# electric-imp-shield.net
KiCad netlist of a schematic drawn in EAGLE
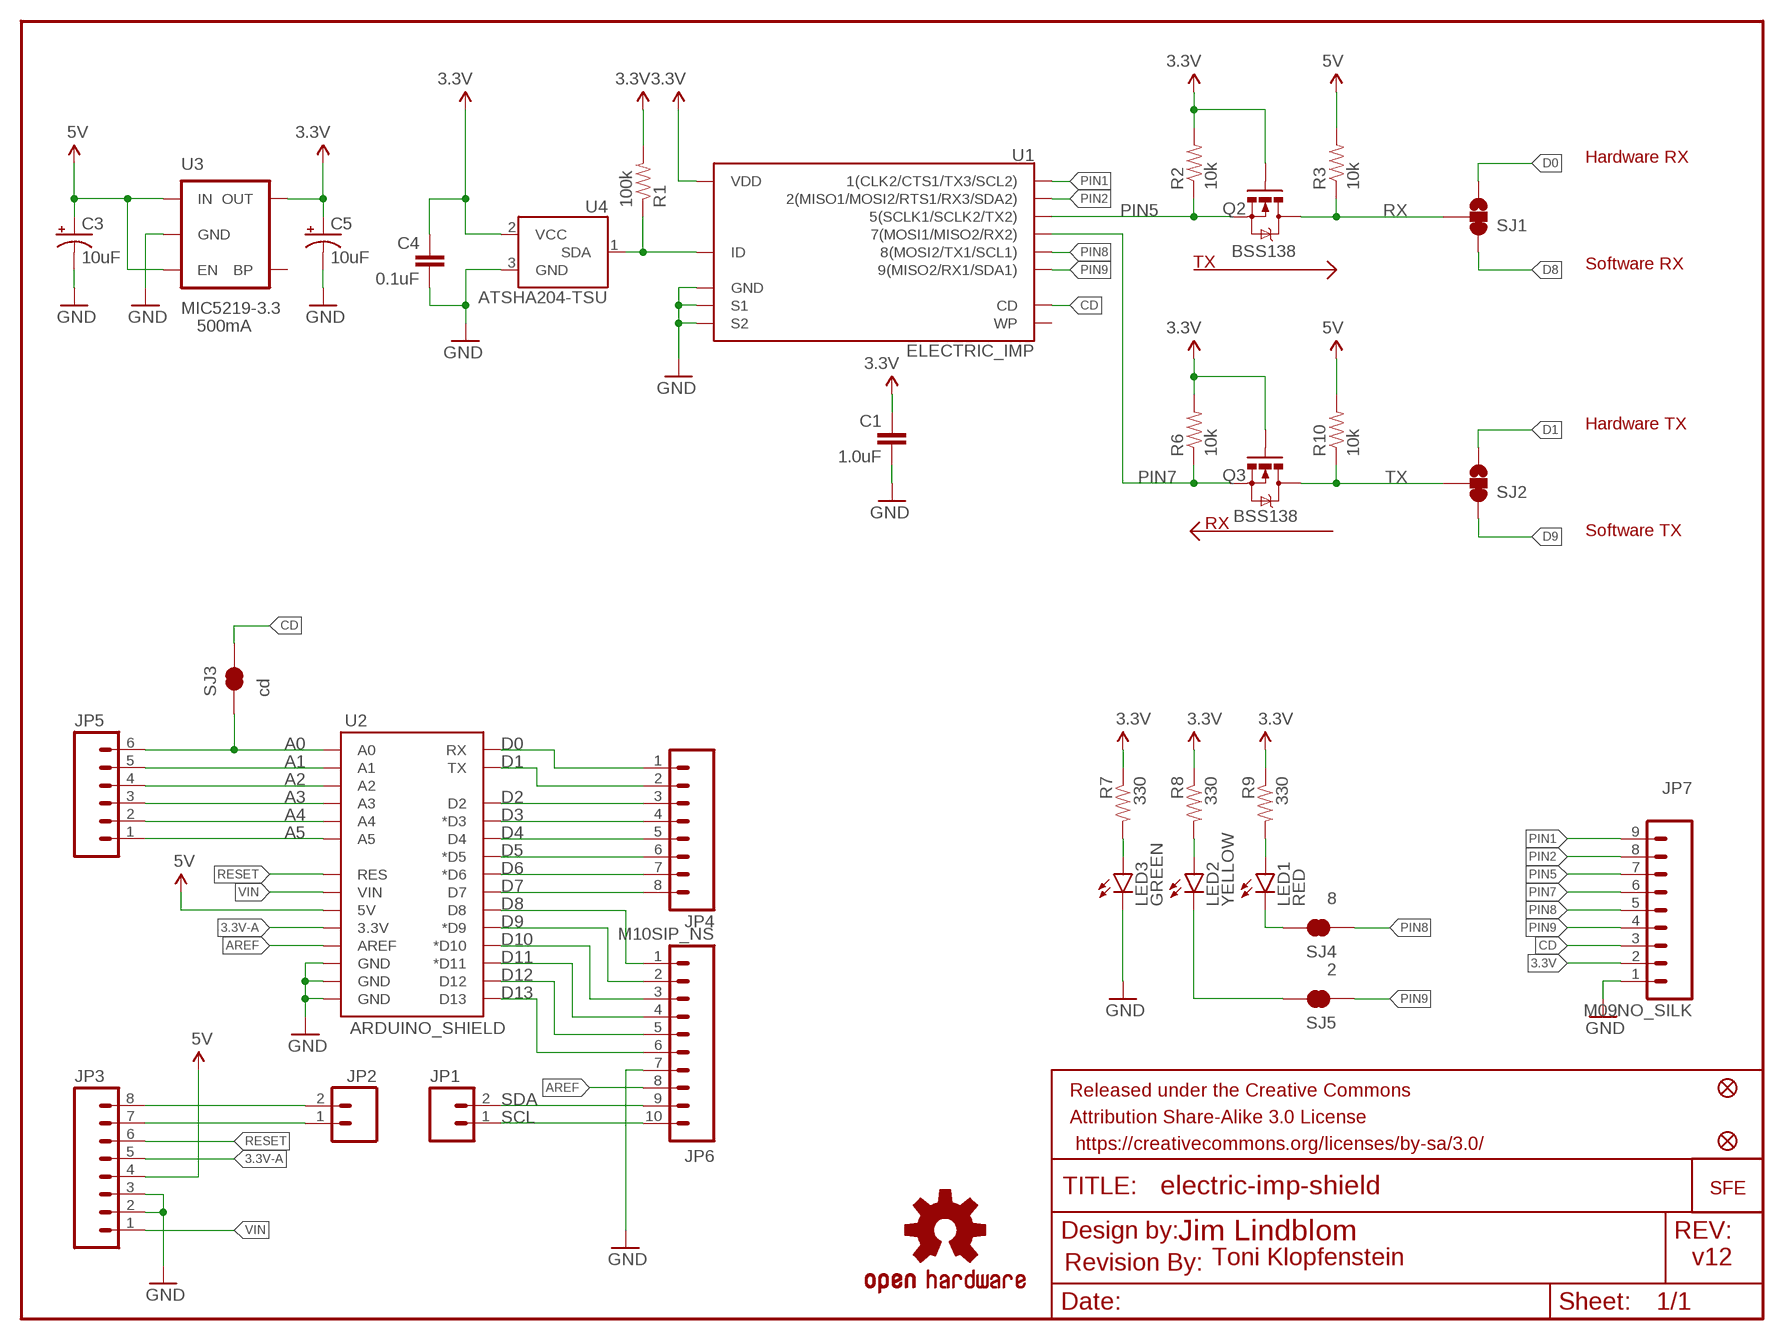
[diagram p0: schematic, sheet 1]

(export (version "E")
  (design (tool "Eeschema 10.0.6"))
  (components
    (comp (ref "C1")
      (value "1.0uF")
      (footprint "eagle-import:0603-CAP")
      (libsource (lib "eagle-import") (part "1.0UF-16V-10%(0603)"))
    )
    (comp (ref "C3")
      (value "10uF")
      (footprint "eagle-import:EIA3216")
      (libsource (lib "eagle-import") (part "10UF-16V-10%(TANT)"))
    )
    (comp (ref "C4")
      (value "0.1uF")
      (footprint "eagle-import:0603-CAP")
      (libsource (lib "eagle-import") (part "0.1UF-25V(+80/-20%)(0603)"))
    )
    (comp (ref "C5")
      (value "10uF")
      (footprint "eagle-import:EIA3216")
      (libsource (lib "eagle-import") (part "10UF-16V-10%(TANT)"))
    )
    (comp (ref "FID1")
      (value "FIDUCIAL1X2")
      (footprint "eagle-import:FIDUCIAL-1X2")
      (libsource (lib "eagle-import") (part "FIDUCIAL1X2"))
    )
    (comp (ref "FID2")
      (value "FIDUCIAL1X2")
      (footprint "eagle-import:FIDUCIAL-1X2")
      (libsource (lib "eagle-import") (part "FIDUCIAL1X2"))
    )
    (comp (ref "FRAME1")
      (value "FRAME-LETTER")
      (footprint "eagle-import:CREATIVE_COMMONS")
      (libsource (lib "eagle-import") (part "FRAME-LETTER"))
    )
    (comp (ref "JP1")
      (value "M021X02_NO_SILK")
      (footprint "eagle-import:1X02_NO_SILK")
      (libsource (lib "eagle-import") (part "M021X02_NO_SILK"))
    )
    (comp (ref "JP2")
      (value "M021X02_NO_SILK")
      (footprint "eagle-import:1X02_NO_SILK")
      (libsource (lib "eagle-import") (part "M021X02_NO_SILK"))
    )
    (comp (ref "JP3")
      (value "M08SIP_NS")
      (footprint "eagle-import:1X08_NO_SILK")
      (libsource (lib "eagle-import") (part "M08SIP_NS"))
    )
    (comp (ref "JP4")
      (value "M08SIP_NS")
      (footprint "eagle-import:1X08_NO_SILK")
      (libsource (lib "eagle-import") (part "M08SIP_NS"))
    )
    (comp (ref "JP5")
      (value "M06SIP_NS")
      (footprint "eagle-import:1X06_NO_SILK")
      (libsource (lib "eagle-import") (part "M06SIP_NS"))
    )
    (comp (ref "JP6")
      (value "M10SIP_NS")
      (footprint "eagle-import:1X10_NO_SILK")
      (libsource (lib "eagle-import") (part "M10SIP_NS"))
    )
    (comp (ref "JP7")
      (value "M09NO_SILK")
      (footprint "eagle-import:1X09_NO_SILK")
      (libsource (lib "eagle-import") (part "M09NO_SILK"))
    )
    (comp (ref "JP10")
      (value "LOGO-SFENW2")
      (footprint "eagle-import:SFE-NEW-WEB")
      (libsource (lib "eagle-import") (part "LOGO-SFENW2"))
    )
    (comp (ref "LED1")
      (value "RED")
      (footprint "eagle-import:LED-0603")
      (libsource (lib "eagle-import") (part "LED-RED0603"))
    )
    (comp (ref "LED2")
      (value "YELLOW")
      (footprint "eagle-import:LED-0603")
      (libsource (lib "eagle-import") (part "LED-YELLOW0603"))
    )
    (comp (ref "LED3")
      (value "GREEN")
      (footprint "eagle-import:LED-0603")
      (libsource (lib "eagle-import") (part "LED-GREEN0603"))
    )
    (comp (ref "Q2")
      (value "BSS138")
      (footprint "eagle-import:SOT23-3")
      (libsource (lib "eagle-import") (part "MOSFET-NCHANNELSMD"))
    )
    (comp (ref "Q3")
      (value "BSS138")
      (footprint "eagle-import:SOT23-3")
      (libsource (lib "eagle-import") (part "MOSFET-NCHANNELSMD"))
    )
    (comp (ref "R1")
      (value "100k")
      (footprint "eagle-import:0603-RES")
      (libsource (lib "eagle-import") (part "100KOHM1/10W1%(0603)"))
    )
    (comp (ref "R2")
      (value "10k")
      (footprint "eagle-import:0603-RES")
      (libsource (lib "eagle-import") (part "10KOHM1/10W1%(0603)0603"))
    )
    (comp (ref "R3")
      (value "10k")
      (footprint "eagle-import:0603-RES")
      (libsource (lib "eagle-import") (part "10KOHM1/10W1%(0603)0603"))
    )
    (comp (ref "R6")
      (value "10k")
      (footprint "eagle-import:0603-RES")
      (libsource (lib "eagle-import") (part "10KOHM1/10W1%(0603)0603"))
    )
    (comp (ref "R7")
      (value "330")
      (footprint "eagle-import:0603-RES")
      (libsource (lib "eagle-import") (part "330OHM1/10W1%(0603)"))
    )
    (comp (ref "R8")
      (value "330")
      (footprint "eagle-import:0603-RES")
      (libsource (lib "eagle-import") (part "330OHM1/10W1%(0603)"))
    )
    (comp (ref "R9")
      (value "330")
      (footprint "eagle-import:0603-RES")
      (libsource (lib "eagle-import") (part "330OHM1/10W1%(0603)"))
    )
    (comp (ref "R10")
      (value "10k")
      (footprint "eagle-import:0603-RES")
      (libsource (lib "eagle-import") (part "10KOHM1/10W1%(0603)0603"))
    )
    (comp (ref "SJ1")
      (value "SOLDERJUMPER_2WAYS")
      (footprint "eagle-import:SJ_3")
      (libsource (lib "eagle-import") (part "SOLDERJUMPER_2WAYS"))
    )
    (comp (ref "SJ2")
      (value "SOLDERJUMPER_2WAYS")
      (footprint "eagle-import:SJ_3")
      (libsource (lib "eagle-import") (part "SOLDERJUMPER_2WAYS"))
    )
    (comp (ref "SJ3")
      (value "cd")
      (footprint "eagle-import:SJ_2S-TRACE")
      (libsource (lib "eagle-import") (part "SOLDERJUMPERTRACE"))
    )
    (comp (ref "SJ4")
      (value "8")
      (footprint "eagle-import:SJ_2S-TRACE")
      (libsource (lib "eagle-import") (part "SOLDERJUMPERTRACE"))
    )
    (comp (ref "SJ5")
      (value "2")
      (footprint "eagle-import:SJ_2S-TRACE")
      (libsource (lib "eagle-import") (part "SOLDERJUMPERTRACE"))
    )
    (comp (ref "U$6")
      (value "REVISION")
      (footprint "eagle-import:REVISION")
      (libsource (lib "eagle-import") (part "REVISION"))
    )
    (comp (ref "U$7")
      (value "OSHW-LOGOS")
      (footprint "eagle-import:OSHW-LOGO-S")
      (libsource (lib "eagle-import") (part "OSHW-LOGOS"))
    )
    (comp (ref "U1")
      (value "ELECTRIC_IMP")
      (footprint "eagle-import:SD_1_1")
      (libsource (lib "eagle-import") (part "ELECTRIC_IMP"))
    )
    (comp (ref "U2")
      (value "ARDUINO_SHIELD")
      (footprint "eagle-import:DUEMILANOVE_SHIELD_NOHOLES_NOLABELS")
      (libsource (lib "eagle-import") (part "ARDUINO_SHIELDNOHOLESORLABELS"))
    )
    (comp (ref "U3")
      (value "MIC5219-3.3")
      (footprint "eagle-import:SOT23-5")
      (libsource (lib "eagle-import") (part "V_REG_LDOSMD"))
    )
    (comp (ref "U4")
      (value "ATSHA204-TSU")
      (footprint "eagle-import:SOT23-3")
      (libsource (lib "eagle-import") (part "ATSHA204-TSU"))
    )
  )
  (nets
    (net (code "1") (name "/A0") (class "Default")
      (node (ref "JP5") (pin "6") (pinfunction "6_6") (pintype "passive"))
      (node (ref "SJ3") (pin "1") (pinfunction "1_1") (pintype "passive"))
      (node (ref "U2") (pin "A0") (pinfunction "A0_A0") (pintype "bidirectional"))
    )
    (net (code "2") (name "/A1") (class "Default")
      (node (ref "JP5") (pin "5") (pinfunction "5_5") (pintype "passive"))
      (node (ref "U2") (pin "A1") (pinfunction "A1_A1") (pintype "bidirectional"))
    )
    (net (code "3") (name "/A2") (class "Default")
      (node (ref "JP5") (pin "4") (pinfunction "4_4") (pintype "passive"))
      (node (ref "U2") (pin "A2") (pinfunction "A2_A2") (pintype "bidirectional"))
    )
    (net (code "4") (name "/A3") (class "Default")
      (node (ref "JP5") (pin "3") (pinfunction "3_3") (pintype "passive"))
      (node (ref "U2") (pin "A3") (pinfunction "A3_A3") (pintype "bidirectional"))
    )
    (net (code "5") (name "/A4") (class "Default")
      (node (ref "JP5") (pin "2") (pinfunction "2_2") (pintype "passive"))
      (node (ref "U2") (pin "A4") (pinfunction "A4_A4") (pintype "bidirectional"))
    )
    (net (code "6") (name "/A5") (class "Default")
      (node (ref "JP5") (pin "1") (pinfunction "1_1") (pintype "passive"))
      (node (ref "U2") (pin "A5") (pinfunction "A5_A5") (pintype "bidirectional"))
    )
    (net (code "7") (name "/D2") (class "Default")
      (node (ref "JP4") (pin "3") (pinfunction "3_3") (pintype "passive"))
      (node (ref "U2") (pin "D2") (pinfunction "D2_D2") (pintype "bidirectional"))
    )
    (net (code "8") (name "/D3") (class "Default")
      (node (ref "JP4") (pin "4") (pinfunction "4_4") (pintype "passive"))
      (node (ref "U2") (pin "D3") (pinfunction "*D3_D3") (pintype "bidirectional"))
    )
    (net (code "9") (name "/D4") (class "Default")
      (node (ref "JP4") (pin "5") (pinfunction "5_5") (pintype "passive"))
      (node (ref "U2") (pin "D4") (pinfunction "D4_D4") (pintype "bidirectional"))
    )
    (net (code "10") (name "/D5") (class "Default")
      (node (ref "JP4") (pin "6") (pinfunction "6_6") (pintype "passive"))
      (node (ref "U2") (pin "D5") (pinfunction "*D5_D5") (pintype "bidirectional"))
    )
    (net (code "11") (name "/D6") (class "Default")
      (node (ref "JP4") (pin "7") (pinfunction "7_7") (pintype "passive"))
      (node (ref "U2") (pin "D6") (pinfunction "*D6_D6") (pintype "bidirectional"))
    )
    (net (code "12") (name "/D7") (class "Default")
      (node (ref "JP4") (pin "8") (pinfunction "8_8") (pintype "passive"))
      (node (ref "U2") (pin "D7") (pinfunction "D7_D7") (pintype "bidirectional"))
    )
    (net (code "13") (name "/D10") (class "Default")
      (node (ref "JP6") (pin "3") (pinfunction "3_3") (pintype "passive"))
      (node (ref "U2") (pin "D10") (pinfunction "*D10_D10") (pintype "bidirectional"))
    )
    (net (code "14") (name "/D11") (class "Default")
      (node (ref "JP6") (pin "4") (pinfunction "4_4") (pintype "passive"))
      (node (ref "U2") (pin "D11") (pinfunction "*D11_D11") (pintype "bidirectional"))
    )
    (net (code "15") (name "/D12") (class "Default")
      (node (ref "JP6") (pin "5") (pinfunction "5_5") (pintype "passive"))
      (node (ref "U2") (pin "D12") (pinfunction "D12_D12") (pintype "bidirectional"))
    )
    (net (code "16") (name "/D13") (class "Default")
      (node (ref "JP6") (pin "6") (pinfunction "6_6") (pintype "passive"))
      (node (ref "U2") (pin "D13") (pinfunction "D13_D13") (pintype "bidirectional"))
    )
    (net (code "17") (name "/RX") (class "Default")
      (node (ref "Q2") (pin "3") (pinfunction "D_3") (pintype "passive"))
      (node (ref "R3") (pin "1") (pinfunction "1_1") (pintype "passive"))
      (node (ref "SJ1") (pin "2") (pinfunction "2_2") (pintype "passive"))
    )
    (net (code "18") (name "/SCL") (class "Default")
      (node (ref "JP1") (pin "1") (pinfunction "1_1") (pintype "passive"))
      (node (ref "JP6") (pin "10") (pinfunction "10_10") (pintype "passive"))
    )
    (net (code "19") (name "/SDA") (class "Default")
      (node (ref "JP1") (pin "2") (pinfunction "2_2") (pintype "passive"))
      (node (ref "JP6") (pin "9") (pinfunction "9_9") (pintype "passive"))
    )
    (net (code "20") (name "/TX") (class "Default")
      (node (ref "Q3") (pin "3") (pinfunction "D_3") (pintype "passive"))
      (node (ref "R10") (pin "1") (pinfunction "1_1") (pintype "passive"))
      (node (ref "SJ2") (pin "2") (pinfunction "2_2") (pintype "passive"))
    )
    (net (code "21") (name "3.3V") (class "Default")
      (node (ref "C1") (pin "1") (pinfunction "1_1") (pintype "passive"))
      (node (ref "C4") (pin "1") (pinfunction "1_1") (pintype "passive"))
      (node (ref "C5") (pin "A") (pinfunction "+_A") (pintype "passive"))
      (node (ref "JP7") (pin "2") (pinfunction "2_2") (pintype "passive"))
      (node (ref "Q2") (pin "1") (pinfunction "G_1") (pintype "passive"))
      (node (ref "Q3") (pin "1") (pinfunction "G_1") (pintype "passive"))
      (node (ref "R1") (pin "2") (pinfunction "2_2") (pintype "passive"))
      (node (ref "R2") (pin "2") (pinfunction "2_2") (pintype "passive"))
      (node (ref "R6") (pin "2") (pinfunction "2_2") (pintype "passive"))
      (node (ref "R7") (pin "1") (pinfunction "1_1") (pintype "passive"))
      (node (ref "R8") (pin "1") (pinfunction "1_1") (pintype "passive"))
      (node (ref "R9") (pin "1") (pinfunction "1_1") (pintype "passive"))
      (node (ref "U1") (pin "4") (pinfunction "VDD_4") (pintype "bidirectional"))
      (node (ref "U3") (pin "5") (pinfunction "OUT_5") (pintype "passive"))
      (node (ref "U4") (pin "2") (pinfunction "VCC_2") (pintype "bidirectional"))
    )
    (net (code "22") (name "3.3V-A") (class "Default")
      (node (ref "JP3") (pin "5") (pinfunction "5_5") (pintype "passive"))
      (node (ref "U2") (pin "3.3V") (pinfunction "3.3V_3.3V") (pintype "bidirectional"))
    )
    (net (code "23") (name "5V") (class "Default")
      (node (ref "C3") (pin "A") (pinfunction "+_A") (pintype "passive"))
      (node (ref "JP3") (pin "4") (pinfunction "4_4") (pintype "passive"))
      (node (ref "R10") (pin "2") (pinfunction "2_2") (pintype "passive"))
      (node (ref "R3") (pin "2") (pinfunction "2_2") (pintype "passive"))
      (node (ref "U2") (pin "5V") (pinfunction "5V_5V") (pintype "bidirectional"))
      (node (ref "U3") (pin "1") (pinfunction "IN_1") (pintype "input"))
      (node (ref "U3") (pin "3") (pinfunction "EN_3") (pintype "input"))
    )
    (net (code "24") (name "AREF") (class "Default")
      (node (ref "JP6") (pin "8") (pinfunction "8_8") (pintype "passive"))
      (node (ref "U2") (pin "AREF") (pinfunction "AREF_AREF") (pintype "bidirectional"))
    )
    (net (code "25") (name "CD") (class "Default")
      (node (ref "JP7") (pin "3") (pinfunction "3_3") (pintype "passive"))
      (node (ref "SJ3") (pin "2") (pinfunction "2_2") (pintype "passive"))
      (node (ref "U1") (pin "CD") (pinfunction "CD_CD") (pintype "bidirectional"))
    )
    (net (code "26") (name "D0") (class "Default")
      (node (ref "JP4") (pin "1") (pinfunction "1_1") (pintype "passive"))
      (node (ref "SJ1") (pin "3") (pinfunction "3_3") (pintype "passive"))
      (node (ref "U2") (pin "RX") (pinfunction "RX_RX") (pintype "bidirectional"))
    )
    (net (code "27") (name "D1") (class "Default")
      (node (ref "JP4") (pin "2") (pinfunction "2_2") (pintype "passive"))
      (node (ref "SJ2") (pin "3") (pinfunction "3_3") (pintype "passive"))
      (node (ref "U2") (pin "TX") (pinfunction "TX_TX") (pintype "bidirectional"))
    )
    (net (code "28") (name "D8") (class "Default")
      (node (ref "JP6") (pin "1") (pinfunction "1_1") (pintype "passive"))
      (node (ref "SJ1") (pin "1") (pinfunction "1_1") (pintype "passive"))
      (node (ref "U2") (pin "D8") (pinfunction "D8_D8") (pintype "bidirectional"))
    )
    (net (code "29") (name "D9") (class "Default")
      (node (ref "JP6") (pin "2") (pinfunction "2_2") (pintype "passive"))
      (node (ref "SJ2") (pin "1") (pinfunction "1_1") (pintype "passive"))
      (node (ref "U2") (pin "D9") (pinfunction "*D9_D9") (pintype "bidirectional"))
    )
    (net (code "30") (name "GND") (class "Default")
      (node (ref "C1") (pin "2") (pinfunction "2_2") (pintype "passive"))
      (node (ref "C3") (pin "C") (pinfunction "-_C") (pintype "passive"))
      (node (ref "C4") (pin "2") (pinfunction "2_2") (pintype "passive"))
      (node (ref "C5") (pin "C") (pinfunction "-_C") (pintype "passive"))
      (node (ref "JP3") (pin "2") (pinfunction "2_2") (pintype "passive"))
      (node (ref "JP3") (pin "3") (pinfunction "3_3") (pintype "passive"))
      (node (ref "JP6") (pin "7") (pinfunction "7_7") (pintype "passive"))
      (node (ref "JP7") (pin "1") (pinfunction "1_1") (pintype "passive"))
      (node (ref "LED3") (pin "C") (pinfunction "C_C") (pintype "passive"))
      (node (ref "U1") (pin "3") (pinfunction "GND_3") (pintype "bidirectional"))
      (node (ref "U1") (pin "SH@1") (pinfunction "S1_SH@1") (pintype "bidirectional"))
      (node (ref "U1") (pin "SH@2") (pinfunction "S2_SH@2") (pintype "bidirectional"))
      (node (ref "U2") (pin "GND@0") (pinfunction "GND_GND@0") (pintype "bidirectional"))
      (node (ref "U2") (pin "GND@1") (pinfunction "GND_GND@1") (pintype "bidirectional"))
      (node (ref "U2") (pin "GND@2") (pinfunction "GND_GND@2") (pintype "bidirectional"))
      (node (ref "U3") (pin "2") (pinfunction "GND_2") (pintype "input"))
      (node (ref "U4") (pin "3") (pinfunction "GND_3") (pintype "bidirectional"))
    )
    (net (code "31") (name "Net-(JP2-Pad1)") (class "Default")
      (node (ref "JP2") (pin "1") (pinfunction "1_1") (pintype "passive"))
      (node (ref "JP3") (pin "7") (pinfunction "7_7") (pintype "passive"))
    )
    (net (code "32") (name "Net-(JP2-Pad2)") (class "Default")
      (node (ref "JP2") (pin "2") (pinfunction "2_2") (pintype "passive"))
      (node (ref "JP3") (pin "8") (pinfunction "8_8") (pintype "passive"))
    )
    (net (code "33") (name "Net-(LED1-PadA)") (class "Default")
      (node (ref "LED1") (pin "A") (pinfunction "A_A") (pintype "passive"))
      (node (ref "R9") (pin "2") (pinfunction "2_2") (pintype "passive"))
    )
    (net (code "34") (name "Net-(LED1-PadC)") (class "Default")
      (node (ref "LED1") (pin "C") (pinfunction "C_C") (pintype "passive"))
      (node (ref "SJ4") (pin "2") (pinfunction "2_2") (pintype "passive"))
    )
    (net (code "35") (name "Net-(LED2-PadA)") (class "Default")
      (node (ref "LED2") (pin "A") (pinfunction "A_A") (pintype "passive"))
      (node (ref "R8") (pin "2") (pinfunction "2_2") (pintype "passive"))
    )
    (net (code "36") (name "Net-(LED2-PadC)") (class "Default")
      (node (ref "LED2") (pin "C") (pinfunction "C_C") (pintype "passive"))
      (node (ref "SJ5") (pin "2") (pinfunction "2_2") (pintype "passive"))
    )
    (net (code "37") (name "Net-(LED3-PadA)") (class "Default")
      (node (ref "LED3") (pin "A") (pinfunction "A_A") (pintype "passive"))
      (node (ref "R7") (pin "2") (pinfunction "2_2") (pintype "passive"))
    )
    (net (code "38") (name "Net-(U1-ID)") (class "Default")
      (node (ref "R1") (pin "1") (pinfunction "1_1") (pintype "passive"))
      (node (ref "U1") (pin "6") (pinfunction "ID_6") (pintype "bidirectional"))
      (node (ref "U4") (pin "1") (pinfunction "SDA_1") (pintype "bidirectional"))
    )
    (net (code "39") (name "PIN1") (class "Default")
      (node (ref "JP7") (pin "9") (pinfunction "9_9") (pintype "passive"))
      (node (ref "U1") (pin "1") (pinfunction "1(CLK2/CTS1/TX3/SCL2)_1") (pintype "bidirectional"))
    )
    (net (code "40") (name "PIN2") (class "Default")
      (node (ref "JP7") (pin "8") (pinfunction "8_8") (pintype "passive"))
      (node (ref "U1") (pin "2") (pinfunction "2(MISO1/MOSI2/RTS1/RX3/SDA2)_2") (pintype "bidirectional"))
    )
    (net (code "41") (name "PIN5") (class "Default")
      (node (ref "JP7") (pin "7") (pinfunction "7_7") (pintype "passive"))
      (node (ref "Q2") (pin "2") (pinfunction "S_2") (pintype "passive"))
      (node (ref "R2") (pin "1") (pinfunction "1_1") (pintype "passive"))
      (node (ref "U1") (pin "5") (pinfunction "5(SCLK1/SCLK2/TX2)_5") (pintype "bidirectional"))
    )
    (net (code "42") (name "PIN7") (class "Default")
      (node (ref "JP7") (pin "6") (pinfunction "6_6") (pintype "passive"))
      (node (ref "Q3") (pin "2") (pinfunction "S_2") (pintype "passive"))
      (node (ref "R6") (pin "1") (pinfunction "1_1") (pintype "passive"))
      (node (ref "U1") (pin "7") (pinfunction "7(MOSI1/MISO2/RX2)_7") (pintype "bidirectional"))
    )
    (net (code "43") (name "PIN8") (class "Default")
      (node (ref "JP7") (pin "5") (pinfunction "5_5") (pintype "passive"))
      (node (ref "SJ4") (pin "1") (pinfunction "1_1") (pintype "passive"))
      (node (ref "U1") (pin "8") (pinfunction "8(MOSI2/TX1/SCL1)_8") (pintype "bidirectional"))
    )
    (net (code "44") (name "PIN9") (class "Default")
      (node (ref "JP7") (pin "4") (pinfunction "4_4") (pintype "passive"))
      (node (ref "SJ5") (pin "1") (pinfunction "1_1") (pintype "passive"))
      (node (ref "U1") (pin "9") (pinfunction "9(MISO2/RX1/SDA1)_9") (pintype "bidirectional"))
    )
    (net (code "45") (name "RESET") (class "Default")
      (node (ref "JP3") (pin "6") (pinfunction "6_6") (pintype "passive"))
      (node (ref "U2") (pin "RES") (pinfunction "RES_RES") (pintype "bidirectional"))
    )
    (net (code "46") (name "VIN") (class "Default")
      (node (ref "JP3") (pin "1") (pinfunction "1_1") (pintype "passive"))
      (node (ref "U2") (pin "VIN") (pinfunction "VIN_VIN") (pintype "bidirectional"))
    )
    (net (code "47") (name "unconnected-(U1-PadWP)") (class "Default")
      (node (ref "U1") (pin "WP") (pinfunction "WP_WP") (pintype "bidirectional"))
    )
    (net (code "48") (name "unconnected-(U3-BP-Pad4)") (class "Default")
      (node (ref "U3") (pin "4") (pinfunction "BP_4") (pintype "input"))
    )
  )
)
